# tracksoar_chip_shield.net
KiCad netlist of a schematic drawn in EAGLE
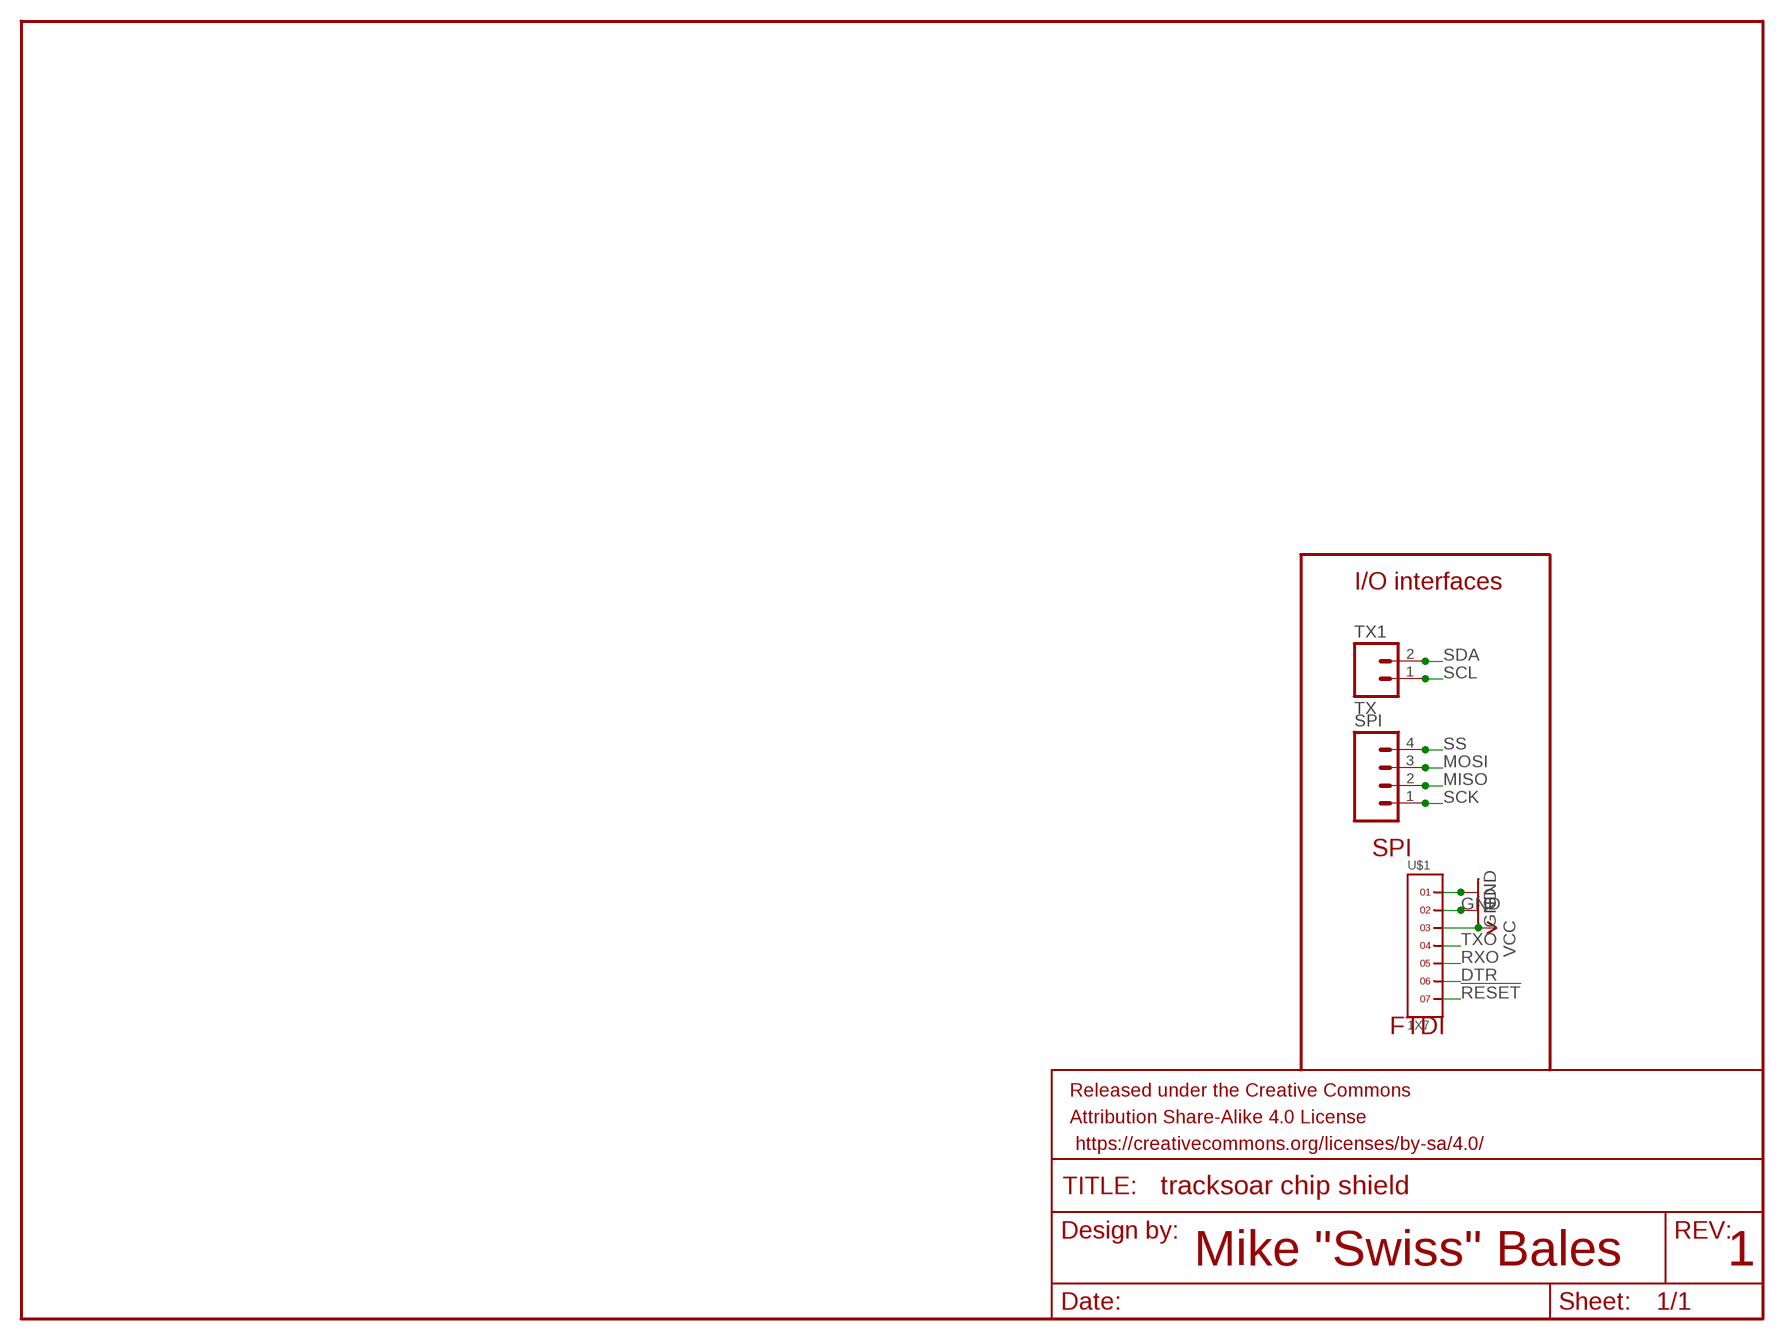
[diagram p0: schematic, sheet 1]

(export (version "E")
  (design (tool "Eeschema 10.0.6"))
  (components
    (comp (ref "FRAME1")
      (value "FRAME-LETTER")
      (footprint "eagle-import:CREATIVE_COMMONS")
      (libsource (lib "eagle-import") (part "FRAME-LETTER"))
    )
    (comp (ref "SPI")
      (value "M04JST-PTH-VERT")
      (footprint "eagle-import:JST-4-PTH-VERT")
      (libsource (lib "eagle-import") (part "M04JST-PTH-VERT"))
    )
    (comp (ref "TX1")
      (value "TX")
      (footprint "eagle-import:JST-2-PTH-VERT")
      (libsource (lib "eagle-import") (part "M02JST-PTH-VERT"))
    )
    (comp (ref "U$1")
      (value "1X7")
      (footprint "eagle-import:1X7")
      (libsource (lib "eagle-import") (part "1X7"))
    )
  )
  (nets
    (net (code "1") (name "/DTR") (class "Default")
      (node (ref "U$1") (pin "6") (pinfunction "6_6") (pintype "bidirectional"))
    )
    (net (code "2") (name "/MISO") (class "Default")
      (node (ref "SPI") (pin "2") (pinfunction "2_2") (pintype "passive"))
    )
    (net (code "3") (name "/MOSI") (class "Default")
      (node (ref "SPI") (pin "3") (pinfunction "3_3") (pintype "passive"))
    )
    (net (code "4") (name "/RXO") (class "Default")
      (node (ref "U$1") (pin "5") (pinfunction "5_5") (pintype "bidirectional"))
    )
    (net (code "5") (name "/SCK") (class "Default")
      (node (ref "SPI") (pin "1") (pinfunction "1_1") (pintype "passive"))
    )
    (net (code "6") (name "/SCL") (class "Default")
      (node (ref "TX1") (pin "1") (pinfunction "1_1") (pintype "passive"))
    )
    (net (code "7") (name "/SDA") (class "Default")
      (node (ref "TX1") (pin "2") (pinfunction "2_2") (pintype "passive"))
    )
    (net (code "8") (name "/SS") (class "Default")
      (node (ref "SPI") (pin "4") (pinfunction "4_4") (pintype "passive"))
    )
    (net (code "9") (name "/TXO") (class "Default")
      (node (ref "U$1") (pin "4") (pinfunction "4_4") (pintype "bidirectional"))
    )
    (net (code "10") (name "/~{RESET}") (class "Default")
      (node (ref "U$1") (pin "7") (pinfunction "7_7") (pintype "bidirectional"))
    )
    (net (code "11") (name "GND") (class "Default")
      (node (ref "U$1") (pin "1") (pinfunction "1_1") (pintype "bidirectional"))
      (node (ref "U$1") (pin "2") (pinfunction "2_2") (pintype "bidirectional"))
    )
    (net (code "12") (name "VCC") (class "Default")
      (node (ref "U$1") (pin "3") (pinfunction "3_3") (pintype "bidirectional"))
    )
  )
)
